# Display-KeyboardModule_v8.net
KiCad netlist of a schematic drawn in EAGLE
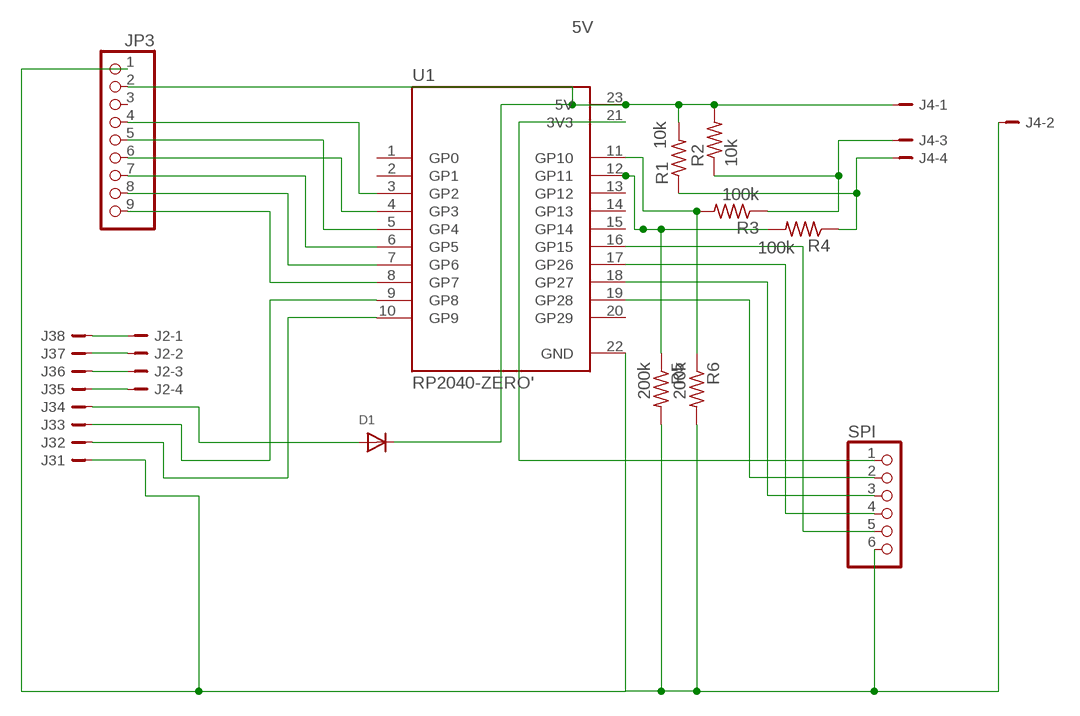
[diagram p0: schematic, sheet 1]

(export (version "E")
  (design (tool "Eeschema 10.0.6"))
  (components
    (comp (ref "D1")
      (value "DIODESMA")
      (footprint "eagle-import:SMADIODE")
      (libsource (lib "eagle-import") (part "DIODESMA"))
    )
    (comp (ref "J2")
      (value "JST-PH-4_TH-RA")
      (footprint "eagle-import:S4B-PH-KL")
      (fields (field (name "MF") "JST") (field (name "MPN") "S4B-PH-KL"))
      (libsource (lib "eagle-import") (part "JST-PH-4_TH-RA"))
    )
    (comp (ref "J3")
      (value "B8B-PH-K-S")
      (footprint "eagle-import:B8B-PH-K-S")
      (libsource (lib "eagle-import") (part "B8B-PH-K-S"))
    )
    (comp (ref "J4")
      (value "JST-PH-4_TH-RA")
      (footprint "eagle-import:S4B-PH-KL")
      (fields (field (name "MF") "JST") (field (name "MPN") "S4B-PH-KL"))
      (libsource (lib "eagle-import") (part "JST-PH-4_TH-RA"))
    )
    (comp (ref "JP3")
      (value "PINHD-1X9")
      (footprint "eagle-import:1X09-BIG")
      (libsource (lib "eagle-import") (part "PINHD-1X9"))
    )
    (comp (ref "R1")
      (value "10k")
      (footprint "eagle-import:R1206")
      (libsource (lib "eagle-import") (part "R-US_R1206"))
    )
    (comp (ref "R2")
      (value "10k")
      (footprint "eagle-import:R1206")
      (libsource (lib "eagle-import") (part "R-US_R1206"))
    )
    (comp (ref "R3")
      (value "100k")
      (footprint "eagle-import:R1206")
      (libsource (lib "eagle-import") (part "R-US_R1206"))
    )
    (comp (ref "R4")
      (value "100k")
      (footprint "eagle-import:R1206")
      (libsource (lib "eagle-import") (part "R-US_R1206"))
    )
    (comp (ref "R5")
      (value "200k")
      (footprint "eagle-import:R1206")
      (libsource (lib "eagle-import") (part "R-US_R1206"))
    )
    (comp (ref "R6")
      (value "200k")
      (footprint "eagle-import:R1206")
      (libsource (lib "eagle-import") (part "R-US_R1206"))
    )
    (comp (ref "SPI")
      (value "PINHD-1X6")
      (footprint "eagle-import:1X06")
      (libsource (lib "eagle-import") (part "PINHD-1X6"))
    )
    (comp (ref "U1")
      (value "RP2040-ZERO'")
      (footprint "eagle-import:MODULE_RP2040-ZERO")
      (fields (field (name "MF") "Waveshare Electronics") (field (name "MP") "RP2040-ZERO"))
      (libsource (lib "eagle-import") (part "RP2040-ZERO'"))
    )
  )
  (nets
    (net (code "1") (name "/5V") (class "Default")
      (node (ref "D1") (pin "C") (pinfunction "C_C") (pintype "passive"))
      (node (ref "J4") (pin "1") (pinfunction "1_1") (pintype "passive"))
      (node (ref "JP3") (pin "2") (pinfunction "2_2") (pintype "passive"))
      (node (ref "R1") (pin "2") (pinfunction "2_2") (pintype "passive"))
      (node (ref "R2") (pin "2") (pinfunction "2_2") (pintype "passive"))
      (node (ref "U1") (pin "23") (pinfunction "5V_23") (pintype "power_in"))
    )
    (net (code "2") (name "Net-(J2B-1)") (class "Default")
      (node (ref "J2") (pin "2") (pinfunction "1_2") (pintype "passive"))
      (node (ref "J3") (pin "7") (pinfunction "1_7") (pintype "passive"))
    )
    (net (code "3") (name "Net-(J2C-1)") (class "Default")
      (node (ref "J2") (pin "3") (pinfunction "1_3") (pintype "passive"))
      (node (ref "J3") (pin "6") (pinfunction "1_6") (pintype "passive"))
    )
    (net (code "4") (name "Net-(J2D-1)") (class "Default")
      (node (ref "J2") (pin "4") (pinfunction "1_4") (pintype "passive"))
      (node (ref "J3") (pin "5") (pinfunction "1_5") (pintype "passive"))
    )
    (net (code "5") (name "Net-(J3B-1)") (class "Default")
      (node (ref "J3") (pin "2") (pinfunction "1_2") (pintype "passive"))
      (node (ref "U1") (pin "10") (pinfunction "GP9_10") (pintype "bidirectional"))
    )
    (net (code "6") (name "Net-(J3C-1)") (class "Default")
      (node (ref "J3") (pin "3") (pinfunction "1_3") (pintype "passive"))
      (node (ref "U1") (pin "9") (pinfunction "GP8_9") (pintype "bidirectional"))
    )
    (net (code "7") (name "Net-(J3D-1)") (class "Default")
      (node (ref "D1") (pin "A") (pinfunction "A_A") (pintype "passive"))
      (node (ref "J3") (pin "4") (pinfunction "1_4") (pintype "passive"))
    )
    (net (code "8") (name "Net-(J3H-1)") (class "Default")
      (node (ref "J2") (pin "1") (pinfunction "1_1") (pintype "passive"))
      (node (ref "J3") (pin "8") (pinfunction "1_8") (pintype "passive"))
    )
    (net (code "9") (name "Net-(J4B-1)") (class "Default")
      (node (ref "J3") (pin "1") (pinfunction "1_1") (pintype "passive"))
      (node (ref "J4") (pin "2") (pinfunction "1_2") (pintype "passive"))
      (node (ref "JP3") (pin "1") (pinfunction "1_1") (pintype "passive"))
      (node (ref "R5") (pin "2") (pinfunction "2_2") (pintype "passive"))
      (node (ref "R6") (pin "2") (pinfunction "2_2") (pintype "passive"))
      (node (ref "SPI") (pin "6") (pinfunction "6_6") (pintype "passive"))
      (node (ref "U1") (pin "22") (pinfunction "GND_22") (pintype "power_in"))
    )
    (net (code "10") (name "Net-(J4C-1)") (class "Default")
      (node (ref "J4") (pin "3") (pinfunction "1_3") (pintype "passive"))
      (node (ref "R2") (pin "1") (pinfunction "1_1") (pintype "passive"))
      (node (ref "R3") (pin "1") (pinfunction "1_1") (pintype "passive"))
    )
    (net (code "11") (name "Net-(J4D-1)") (class "Default")
      (node (ref "J4") (pin "4") (pinfunction "1_4") (pintype "passive"))
      (node (ref "R1") (pin "1") (pinfunction "1_1") (pintype "passive"))
      (node (ref "R4") (pin "1") (pinfunction "1_1") (pintype "passive"))
    )
    (net (code "12") (name "Net-(U1-3V3)") (class "Default")
      (node (ref "SPI") (pin "1") (pinfunction "1_1") (pintype "passive"))
      (node (ref "U1") (pin "21") (pinfunction "3V3_21") (pintype "power_in"))
    )
    (net (code "13") (name "Net-(U1-GP2)") (class "Default")
      (node (ref "JP3") (pin "4") (pinfunction "4_4") (pintype "passive"))
      (node (ref "U1") (pin "3") (pinfunction "GP2_3") (pintype "bidirectional"))
    )
    (net (code "14") (name "Net-(U1-GP3)") (class "Default")
      (node (ref "JP3") (pin "6") (pinfunction "6_6") (pintype "passive"))
      (node (ref "U1") (pin "4") (pinfunction "GP3_4") (pintype "bidirectional"))
    )
    (net (code "15") (name "Net-(U1-GP4)") (class "Default")
      (node (ref "JP3") (pin "5") (pinfunction "5_5") (pintype "passive"))
      (node (ref "U1") (pin "5") (pinfunction "GP4_5") (pintype "bidirectional"))
    )
    (net (code "16") (name "Net-(U1-GP5)") (class "Default")
      (node (ref "JP3") (pin "7") (pinfunction "7_7") (pintype "passive"))
      (node (ref "U1") (pin "6") (pinfunction "GP5_6") (pintype "bidirectional"))
    )
    (net (code "17") (name "Net-(U1-GP6)") (class "Default")
      (node (ref "JP3") (pin "8") (pinfunction "8_8") (pintype "passive"))
      (node (ref "U1") (pin "7") (pinfunction "GP6_7") (pintype "bidirectional"))
    )
    (net (code "18") (name "Net-(U1-GP7)") (class "Default")
      (node (ref "JP3") (pin "9") (pinfunction "9_9") (pintype "passive"))
      (node (ref "U1") (pin "8") (pinfunction "GP7_8") (pintype "bidirectional"))
    )
    (net (code "19") (name "Net-(U1-GP10)") (class "Default")
      (node (ref "R3") (pin "2") (pinfunction "2_2") (pintype "passive"))
      (node (ref "R6") (pin "1") (pinfunction "1_1") (pintype "passive"))
      (node (ref "U1") (pin "11") (pinfunction "GP10_11") (pintype "bidirectional"))
    )
    (net (code "20") (name "Net-(U1-GP11)") (class "Default")
      (node (ref "R4") (pin "2") (pinfunction "2_2") (pintype "passive"))
      (node (ref "R5") (pin "1") (pinfunction "1_1") (pintype "passive"))
      (node (ref "U1") (pin "12") (pinfunction "GP11_12") (pintype "bidirectional"))
    )
    (net (code "21") (name "Net-(U1-GP15)") (class "Default")
      (node (ref "SPI") (pin "5") (pinfunction "5_5") (pintype "passive"))
      (node (ref "U1") (pin "16") (pinfunction "GP15_16") (pintype "bidirectional"))
    )
    (net (code "22") (name "Net-(U1-GP26)") (class "Default")
      (node (ref "SPI") (pin "4") (pinfunction "4_4") (pintype "passive"))
      (node (ref "U1") (pin "17") (pinfunction "GP26_17") (pintype "bidirectional"))
    )
    (net (code "23") (name "Net-(U1-GP27)") (class "Default")
      (node (ref "SPI") (pin "3") (pinfunction "3_3") (pintype "passive"))
      (node (ref "U1") (pin "18") (pinfunction "GP27_18") (pintype "bidirectional"))
    )
    (net (code "24") (name "Net-(U1-GP28)") (class "Default")
      (node (ref "SPI") (pin "2") (pinfunction "2_2") (pintype "passive"))
      (node (ref "U1") (pin "19") (pinfunction "GP28_19") (pintype "bidirectional"))
    )
    (net (code "25") (name "unconnected-(JP3-Pad3)") (class "Default")
      (node (ref "JP3") (pin "3") (pinfunction "3_3") (pintype "passive"))
    )
    (net (code "26") (name "unconnected-(U1-GP0-Pad1)") (class "Default")
      (node (ref "U1") (pin "1") (pinfunction "GP0_1") (pintype "bidirectional"))
    )
    (net (code "27") (name "unconnected-(U1-GP1-Pad2)") (class "Default")
      (node (ref "U1") (pin "2") (pinfunction "GP1_2") (pintype "bidirectional"))
    )
    (net (code "28") (name "unconnected-(U1-GP12-Pad13)") (class "Default")
      (node (ref "U1") (pin "13") (pinfunction "GP12_13") (pintype "bidirectional"))
    )
    (net (code "29") (name "unconnected-(U1-GP13-Pad14)") (class "Default")
      (node (ref "U1") (pin "14") (pinfunction "GP13_14") (pintype "bidirectional"))
    )
    (net (code "30") (name "unconnected-(U1-GP14-Pad15)") (class "Default")
      (node (ref "U1") (pin "15") (pinfunction "GP14_15") (pintype "bidirectional"))
    )
    (net (code "31") (name "unconnected-(U1-GP29-Pad20)") (class "Default")
      (node (ref "U1") (pin "20") (pinfunction "GP29_20") (pintype "bidirectional"))
    )
  )
)
